# PCB_Master_Traffic_Light.net
KiCad netlist of a schematic drawn in Altium Designer
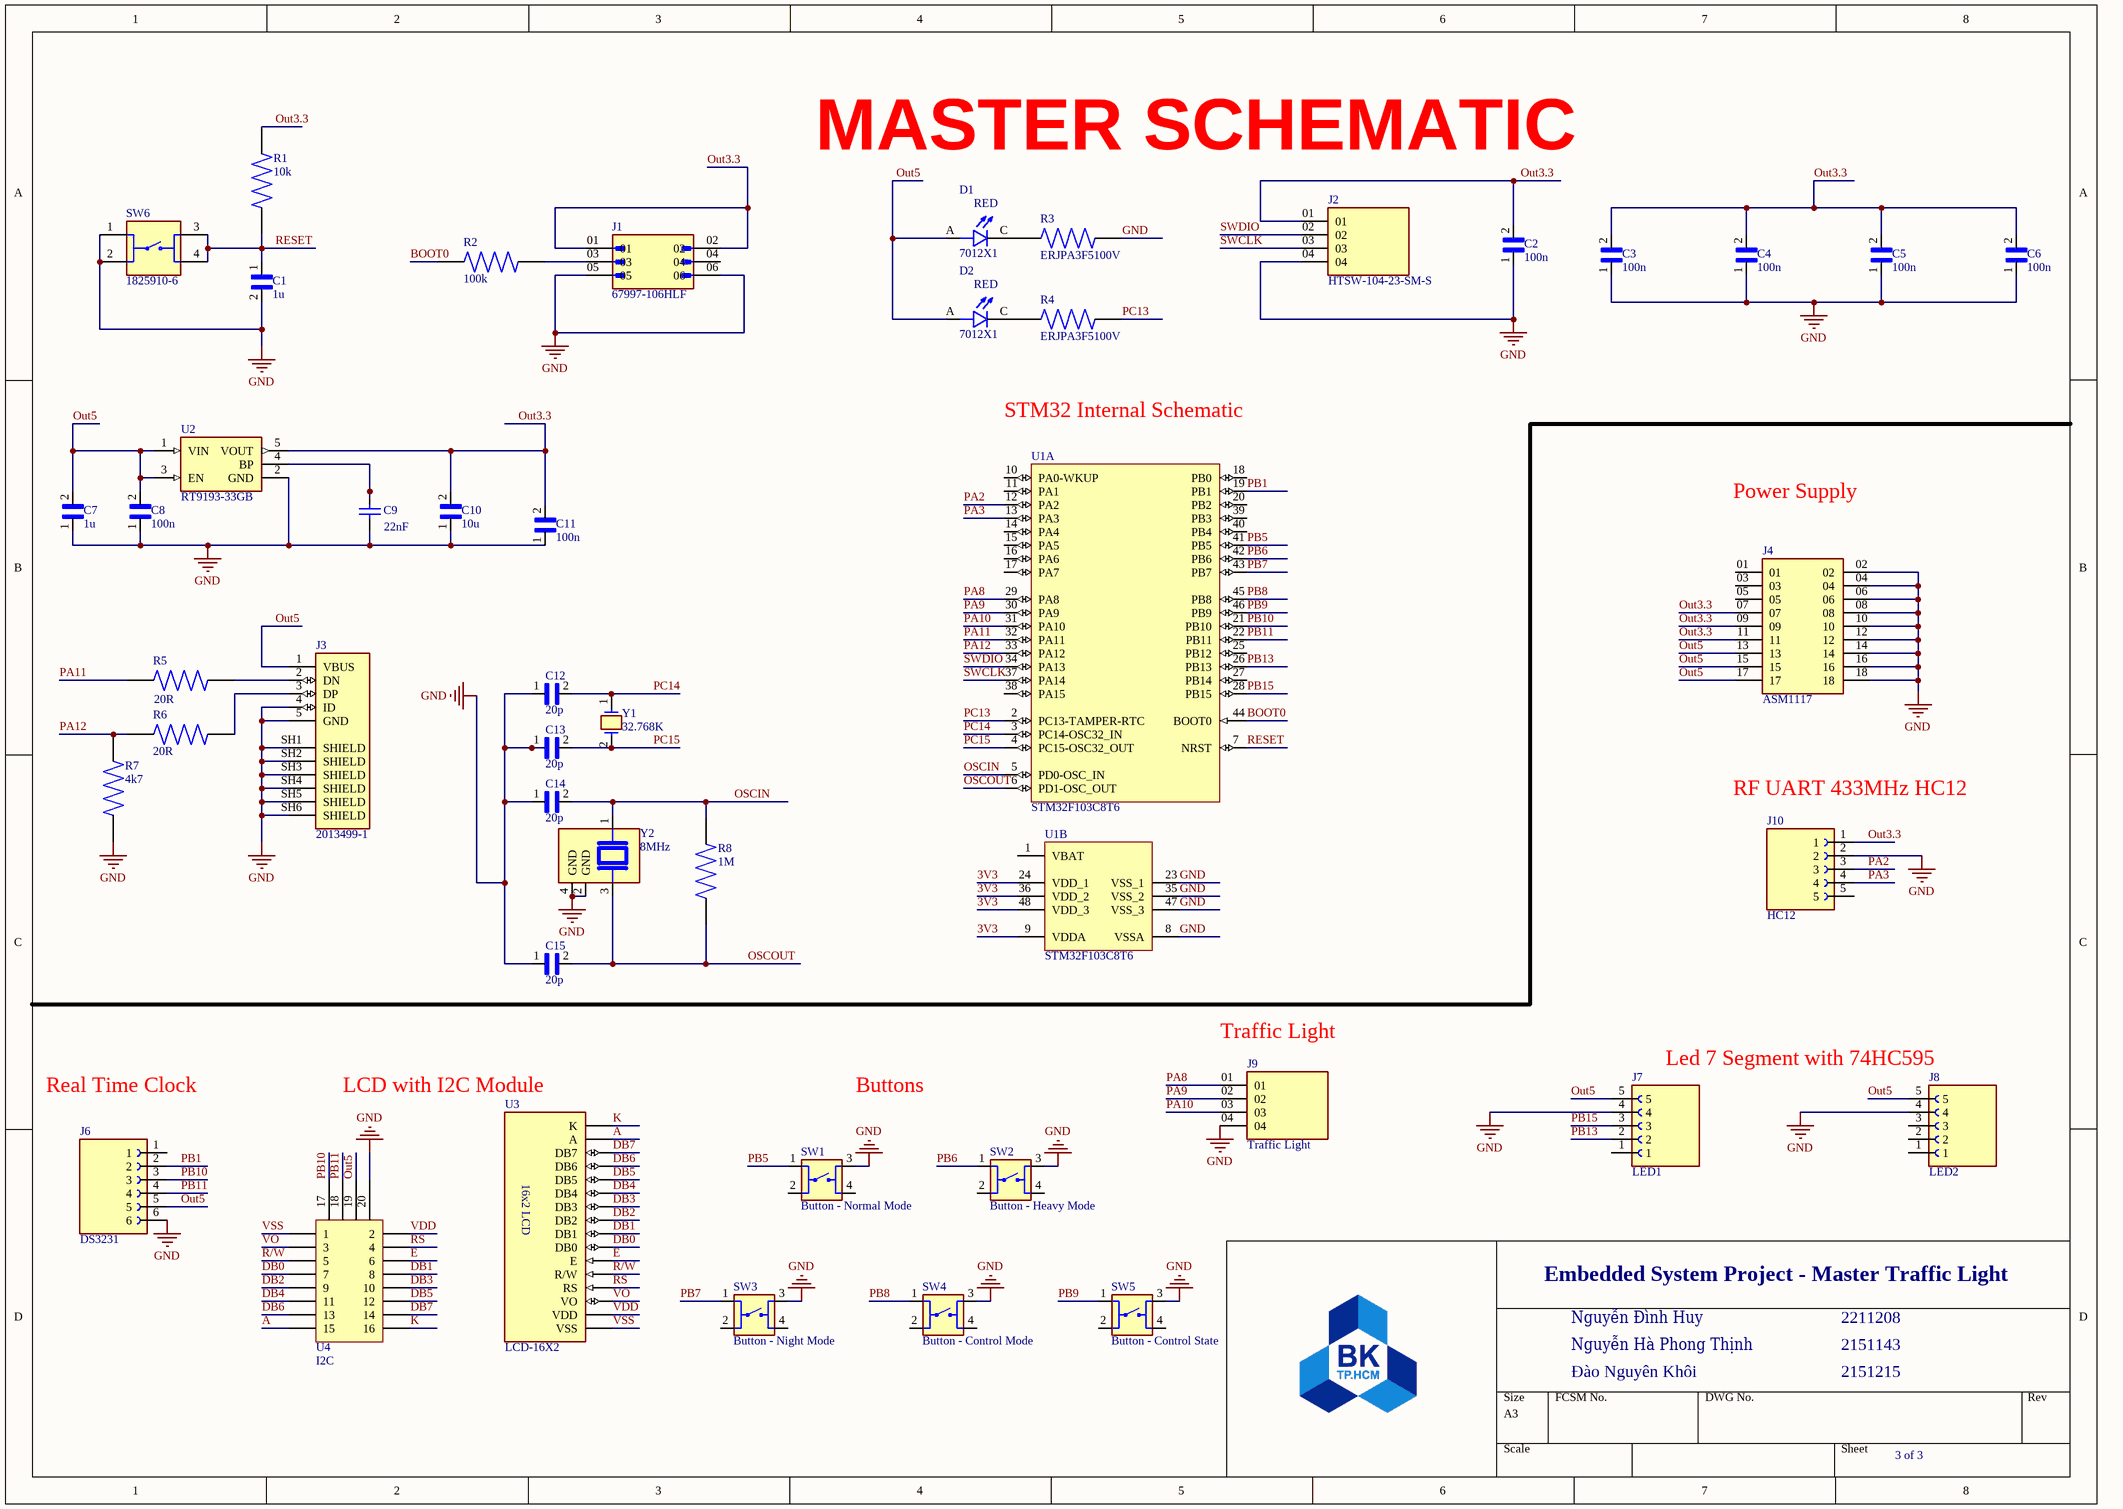
[diagram p0: PCB_Master_Traffic_Light.SchDoc]

(export (version "E")
  (design (tool "Eeschema 10.0.6"))
  (components
    (comp (ref "C1")
      (value "1u")
      (footprint "CAPC2012X145N")
      (description "1 ÂµF Â±10% 25V Ceramic Capacitor X5R 0805 (2012 Metric)")
      (fields (field (name "MF") "TDK") (field (name "DIGI-KEY_PART_NUMBER") "445-1419-2-ND"))
      (libsource (lib "Capacitor 1u") (part "C2012X5R1E105K125AA"))
    )
    (comp (ref "C2")
      (value "100n")
      (footprint "CAPC2012X100N")
      (description "0.1 ÂµF Â±10% 50V Ceramic Capacitor X7R 0805 (2012 Metric)")
      (fields (field (name "MP") "C2012X7R1H104K085AA") (field (name "MF") "TDK"))
      (libsource (lib "Capacitor 100n") (part "C2012X7R1H104K085AA"))
    )
    (comp (ref "C3")
      (value "100n")
      (footprint "CAPC2012X100N")
      (description "0.1 ÂµF Â±10% 50V Ceramic Capacitor X7R 0805 (2012 Metric)")
      (fields (field (name "MP") "C2012X7R1H104K085AA") (field (name "MF") "TDK"))
      (libsource (lib "Capacitor 100n") (part "C2012X7R1H104K085AA"))
    )
    (comp (ref "C4")
      (value "100n")
      (footprint "CAPC2012X100N")
      (description "0.1 ÂµF Â±10% 50V Ceramic Capacitor X7R 0805 (2012 Metric)")
      (fields (field (name "MP") "C2012X7R1H104K085AA") (field (name "MF") "TDK"))
      (libsource (lib "Capacitor 100n") (part "C2012X7R1H104K085AA"))
    )
    (comp (ref "C5")
      (value "100n")
      (footprint "CAPC2012X100N")
      (description "0.1 ÂµF Â±10% 50V Ceramic Capacitor X7R 0805 (2012 Metric)")
      (fields (field (name "MP") "C2012X7R1H104K085AA") (field (name "MF") "TDK"))
      (libsource (lib "Capacitor 100n") (part "C2012X7R1H104K085AA"))
    )
    (comp (ref "C6")
      (value "100n")
      (footprint "CAPC2012X100N")
      (description "0.1 ÂµF Â±10% 50V Ceramic Capacitor X7R 0805 (2012 Metric)")
      (fields (field (name "MP") "C2012X7R1H104K085AA") (field (name "MF") "TDK"))
      (libsource (lib "Capacitor 100n") (part "C2012X7R1H104K085AA"))
    )
    (comp (ref "C7")
      (value "1u")
      (footprint "CAPC2012X145N")
      (description "1 ÂµF Â±10% 25V Ceramic Capacitor X5R 0805 (2012 Metric)")
      (fields (field (name "MF") "TDK") (field (name "DIGI-KEY_PART_NUMBER") "445-1419-2-ND"))
      (libsource (lib "") (part "C2012X5R1E105K125AA_1"))
    )
    (comp (ref "C8")
      (value "100n")
      (footprint "CAPC2012X100N")
      (description "0.1 ÂµF Â±10% 50V Ceramic Capacitor X7R 0805 (2012 Metric)")
      (fields (field (name "MP") "C2012X7R1H104K085AA") (field (name "MF") "TDK"))
      (libsource (lib "Capacitor 100n") (part "C2012X7R1H104K085AA"))
    )
    (comp (ref "C9")
      (value "22nF")
      (footprint "WCAP-CSGP_1812_L4.5W3.2H1.25")
      (description "WCAP-CSGP Multilayer Ceramic Chip Capacitor, General Purpose, size 1812, NP0, 22nF, 50V")
      (fields
        (field (name "MANUFACTURER PART NUMBER") "885012010015")
        (field (name "MANUFACTURER") "Wurth Elektronik")
      )
      (libsource (lib "Capacitor 22n") (part "885012010015"))
    )
    (comp (ref "C10")
      (value "10u")
      (footprint "CAPC2012X100N")
      (description "10ÂµF Â±20% 16V Ceramic Capacitor X5R 0805 (2012 Metric)")
      (fields (field (name "MF") "TDK") (field (name "MP") "C2012X5R1C106M085AC"))
      (libsource (lib "Capacitor 10u") (part "C2012X5R1C106M085AC"))
    )
    (comp (ref "C11")
      (value "100n")
      (footprint "CAPC2012X100N")
      (description "0.1 ÂµF Â±10% 50V Ceramic Capacitor X7R 0805 (2012 Metric)")
      (fields (field (name "MP") "C2012X7R1H104K085AA") (field (name "MF") "TDK"))
      (libsource (lib "Capacitor 100n") (part "C2012X7R1H104K085AA"))
    )
    (comp (ref "C12")
      (value "20p")
      (footprint "CAPC2012X100N")
      (description "SMD Capacitor C0G(EIA) with Capacitance: 20pF Tol. 5%. Rated Voltage: 250Vdc")
      (fields (field (name "MF") "Murata") (field (name "MP") "GQM2195C2E200JB12D"))
      (libsource (lib "Capacitor 20pF") (part "GQM2195C2E200JB12D"))
    )
    (comp (ref "C13")
      (value "20p")
      (footprint "CAPC2012X100N")
      (description "SMD Capacitor C0G(EIA) with Capacitance: 20pF Tol. 5%. Rated Voltage: 250Vdc")
      (fields (field (name "MF") "Murata") (field (name "MP") "GQM2195C2E200JB12D"))
      (libsource (lib "Capacitor 20pF") (part "GQM2195C2E200JB12D"))
    )
    (comp (ref "C14")
      (value "20p")
      (footprint "CAPC2012X100N")
      (description "SMD Capacitor C0G(EIA) with Capacitance: 20pF Tol. 5%. Rated Voltage: 250Vdc")
      (fields (field (name "MF") "Murata") (field (name "MP") "GQM2195C2E200JB12D"))
      (libsource (lib "Capacitor 20pF") (part "GQM2195C2E200JB12D"))
    )
    (comp (ref "C15")
      (value "20p")
      (footprint "CAPC2012X100N")
      (description "SMD Capacitor C0G(EIA) with Capacitance: 20pF Tol. 5%. Rated Voltage: 250Vdc")
      (fields (field (name "MF") "Murata") (field (name "MP") "GQM2195C2E200JB12D"))
      (libsource (lib "Capacitor 20pF") (part "GQM2195C2E200JB12D"))
    )
    (comp (ref "D1")
      (value "7012X1")
      (footprint "LED_7012X1")
      (description "Red - LED Indication - Discrete 1.7V 0805 (2012 Metric)")
      (fields (field (name "MF") "VCC"))
      (libsource (lib "RedLed") (part "7012X1"))
    )
    (comp (ref "D2")
      (value "7012X1")
      (footprint "LED_7012X1")
      (description "Red - LED Indication - Discrete 1.7V 0805 (2012 Metric)")
      (fields (field (name "MF") "VCC"))
      (libsource (lib "RedLed") (part "7012X1"))
    )
    (comp (ref "J1")
      (value "67997-106HLF")
      (footprint "AMPHENOL_67997-106HLF")
      (fields (field (name "MF") "Amphenol ICC"))
      (libsource (lib "Header3x2") (part "67997-106HLF"))
    )
    (comp (ref "J2")
      (value "HTSW-104-23-SM-S")
      (footprint "SAMTEC_HTSW-104-23-SM-S")
      (fields (field (name "MF") "Samtec") (field (name "MP") "HTSW10423SMS"))
      (libsource (lib "Header 4x1") (part "HTSW-104-23-SM-S"))
    )
    (comp (ref "J3")
      (value "2013499-1")
      (footprint "TE_2013499-1")
      (libsource (lib "micro USB") (part "2013499-1"))
    )
    (comp (ref "J4")
      (value "ASM1117")
      (footprint "SAMTEC_MTSW-109-13-G-D-905")
      (fields (field (name "MP") "MTSW-109-13-G-D-905"))
      (libsource (lib "Header 9x2") (part "MTSW-109-13-G-D-905"))
    )
    (comp (ref "J6")
      (value "DS3231")
      (footprint "HARWIN_M20-7820646")
      (fields (field (name "MP") "M20-7820646"))
      (libsource (lib "Header 6x1") (part "M20-7820646"))
    )
    (comp (ref "J7")
      (value "LED1")
      (footprint "HARWIN_M20-7820546")
      (fields (field (name "MP") "M20-7820546"))
      (libsource (lib "") (part "M20-7820546_1"))
    )
    (comp (ref "J8")
      (value "LED2")
      (footprint "HARWIN_M20-7820546")
      (fields (field (name "MP") "M20-7820546"))
      (libsource (lib "") (part "M20-7820546_1"))
    )
    (comp (ref "J9")
      (value "Traffic Light")
      (footprint "SAMTEC_HTSW-104-23-SM-S")
      (fields (field (name "MF") "Samtec") (field (name "MP") "HTSW10423SMS"))
      (libsource (lib "Header 4x1") (part "HTSW-104-23-SM-S"))
    )
    (comp (ref "J10")
      (value "HC12")
      (footprint "HARWIN_M20-7820546")
      (fields (field (name "MP") "M20-7820546"))
      (libsource (lib "Header 5x1") (part "M20-7820546"))
    )
    (comp (ref "R1")
      (value "10k")
      (footprint "RESC2012X60N")
      (description "10 kOhms Â±1% 0.125W, 1/8W Chip Resistor 0805 (2012 Metric) Moisture Resistant Thick Film")
      (fields (field (name "MF") "Yageo") (field (name "MP") "RC0805FR-0710KL"))
      (libsource (lib "RES10k") (part "RC0805FR-0710KL"))
    )
    (comp (ref "R2")
      (value "100k")
      (footprint "RESC2012X60N")
      (description "100 kOhms Â±1% 0.125W, 1/8W Chip Resistor 0805 (2012 Metric) Moisture Resistant Thick Film")
      (fields (field (name "MF") "Yageo") (field (name "MP") "RC0805FR-07100KL"))
      (libsource (lib "RES100k") (part "RC0805FR-07100KL"))
    )
    (comp (ref "R3")
      (value "ERJPA3F5100V")
      (footprint "RES_ERJPA3F5100V")
      (description "RES, THICK FILM, 510R, 1%, 0.25W, 0603")
      (fields (field (name "MF") "Panasonic") (field (name "MP") "ERJ-PA3F5100V"))
      (libsource (lib "RES510") (part "ERJPA3F5100V"))
    )
    (comp (ref "R4")
      (value "ERJPA3F5100V")
      (footprint "RES_ERJPA3F5100V")
      (description "RES, THICK FILM, 510R, 1%, 0.25W, 0603")
      (fields (field (name "MF") "Panasonic") (field (name "MP") "ERJ-PA3F5100V"))
      (libsource (lib "RES510") (part "ERJPA3F5100V"))
    )
    (comp (ref "R5")
      (value "20R")
      (footprint "RESC5025X120N")
      (fields (field (name "MP") "3-2176397-2"))
      (libsource (lib "RES20") (part "3-2176397-2"))
    )
    (comp (ref "R6")
      (value "20R")
      (footprint "RESC5025X120N")
      (fields (field (name "MP") "3-2176397-2"))
      (libsource (lib "RES20") (part "3-2176397-2"))
    )
    (comp (ref "R7")
      (value "4k7")
      (footprint "RESC1608X55N")
      (fields
        (field (name "MF") "TE Connectivity")
        (field (name "MP") "CRG0603F4K7")
        (field (name "TOLERANCE") "1%")
      )
      (libsource (lib "RES4.7k") (part "CRG0603F4K7"))
    )
    (comp (ref "R8")
      (value "1M")
      (footprint "RESC2012X60N")
      (description "1 MOhms Â±1% 0.125W, 1/8W Chip Resistor 0805 (2012 Metric) Moisture Resistant Thick Film")
      (fields (field (name "MF") "Yageo") (field (name "MP") "RC0805FR-071ML"))
      (libsource (lib "RES1M") (part "RC0805FR-071ML"))
    )
    (comp (ref "SW1")
      (value "Button - Normal Mode")
      (footprint "SW_FSM8JH")
      (description "Tactile Switch SPST-NO Top Actuated Through Hole")
      (fields (field (name "MP") "FSM8JH") (field (name "MF") "TE Connectivity"))
      (libsource (lib "Button1") (part "FSM8JH"))
    )
    (comp (ref "SW2")
      (value "Button - Heavy Mode")
      (footprint "SW_FSM8JH")
      (description "Tactile Switch SPST-NO Top Actuated Through Hole")
      (fields (field (name "MP") "FSM8JH") (field (name "MF") "TE Connectivity"))
      (libsource (lib "Button1") (part "FSM8JH"))
    )
    (comp (ref "SW3")
      (value "Button - Night Mode")
      (footprint "SW_FSM8JH")
      (description "Tactile Switch SPST-NO Top Actuated Through Hole")
      (fields (field (name "MP") "FSM8JH") (field (name "MF") "TE Connectivity"))
      (libsource (lib "Button1") (part "FSM8JH"))
    )
    (comp (ref "SW4")
      (value "Button - Control Mode")
      (footprint "SW_FSM8JH")
      (description "Tactile Switch SPST-NO Top Actuated Through Hole")
      (fields (field (name "MP") "FSM8JH") (field (name "MF") "TE Connectivity"))
      (libsource (lib "Button1") (part "FSM8JH"))
    )
    (comp (ref "SW5")
      (value "Button - Control State")
      (footprint "SW_FSM8JH")
      (description "Tactile Switch SPST-NO Top Actuated Through Hole")
      (fields (field (name "MP") "FSM8JH") (field (name "MF") "TE Connectivity"))
      (libsource (lib "Button1") (part "FSM8JH"))
    )
    (comp (ref "SW6")
      (value "1825910-6")
      (footprint "SW_1825910-6-4")
      (description "Switch Push Button OFF (ON) SPST Round Button 0.05A 24VDC Momentary Contact PC Pins Thru-Hole")
      (fields (field (name "MF") "TE Connectivity") (field (name "DIGI-KEY_PART_NUMBER") "450-1650-ND"))
      (libsource (lib "Button") (part "1825910-6"))
    )
    (comp (ref "U1")
      (value "STM32F103C8T6")
      (footprint "STM-LQFP48_L")
      (libsource (lib "STM32F103C8T6") (part "CMP-0237-00215-3"))
    )
    (comp (ref "U2")
      (value "RT9193-33GB")
      (footprint "SOT94P279X129-5N")
      (description "Linear Voltage Regulator IC Positive Fixed 1 Output 300mA TSOT-23-5")
      (fields (field (name "MF") "Richtek USA") (field (name "DIGI-KEY_PART_NUMBER") "1028-1014-2-ND"))
      (libsource (lib "RT9193-33GB") (part "RT9193-33GB"))
    )
    (comp (ref "U3")
      (value "LCD-16X2")
      (footprint "MODULE_LCD-16X2")
      (description "Display Development Tools 16x2 Black on Green Char LCD w Backlight")
      (fields (field (name "MF") "Gravitech"))
      (libsource (lib "LCD-16X2") (part "LCD-16X2"))
    )
    (comp (ref "U4") (value "I2C") (footprint "PCF8574") (libsource (lib "PCF8574") (part "PCF8574")))
    (comp (ref "Y1")
      (value "32.768K")
      (footprint "XTAL_NX3215SA-32.768K-STD-MUA-14")
      (description "32.768kHz Â±20ppm Crystal 6pF 70 kOhms 2-SMD, No Lead  MANUFACTURER: NIHON DEMPA KOGYO")
      (fields (field (name "MP") "NX3215SA-32.768K-STD-MUA-14"))
      (libsource (lib "Crystal 32.768k") (part "NX3215SA-32.768K-STD-MUA-14"))
    )
    (comp (ref "Y2")
      (value "8MHz")
      (footprint "XTAL_ABM3B-8.000MHZ-10-1-U-T")
      (description "8 MHz Â±10ppm Crystal 10pF 200 Ohms 4-SMD, No Lead")
      (fields (field (name "MF") "Abracon") (field (name "MP") "ABM3B-8.000MHZ-10-1-U-T"))
      (libsource (lib "Crystal 8MHz") (part "ABM3B-8.000MHZ-10-1-U-T"))
    )
  )
  (nets
    (net (code "1") (name "/3V3") (class "Default")
      (node (ref "U1") (pin "24") (pinfunction "VDD_1_24") (pintype "power_in"))
      (node (ref "U1") (pin "36") (pinfunction "VDD_2_36") (pintype "power_in"))
      (node (ref "U1") (pin "48") (pinfunction "VDD_3_48") (pintype "power_in"))
      (node (ref "U1") (pin "9") (pinfunction "VDDA_9") (pintype "power_in"))
    )
    (net (code "2") (name "/A") (class "Default")
      (node (ref "U3") (pin "15") (pinfunction "A_15") (pintype "power_in"))
      (node (ref "U4") (pin "15") (pinfunction "15_15") (pintype "passive"))
    )
    (net (code "3") (name "/BOOT0") (class "Default")
      (node (ref "R2") (pin "1") (pinfunction "1_1") (pintype "passive"))
      (node (ref "U1") (pin "44") (pinfunction "BOOT0_44") (pintype "input"))
    )
    (net (code "4") (name "/DB0") (class "Default")
      (node (ref "U3") (pin "7") (pinfunction "DB0_7") (pintype "bidirectional"))
      (node (ref "U4") (pin "7") (pinfunction "7_7") (pintype "passive"))
    )
    (net (code "5") (name "/DB1") (class "Default")
      (node (ref "U3") (pin "8") (pinfunction "DB1_8") (pintype "bidirectional"))
      (node (ref "U4") (pin "8") (pinfunction "8_8") (pintype "passive"))
    )
    (net (code "6") (name "/DB2") (class "Default")
      (node (ref "U3") (pin "9") (pinfunction "DB2_9") (pintype "bidirectional"))
      (node (ref "U4") (pin "9") (pinfunction "9_9") (pintype "passive"))
    )
    (net (code "7") (name "/DB3") (class "Default")
      (node (ref "U3") (pin "10") (pinfunction "DB3_10") (pintype "bidirectional"))
      (node (ref "U4") (pin "10") (pinfunction "10_10") (pintype "passive"))
    )
    (net (code "8") (name "/DB4") (class "Default")
      (node (ref "U3") (pin "11") (pinfunction "DB4_11") (pintype "bidirectional"))
      (node (ref "U4") (pin "11") (pinfunction "11_11") (pintype "passive"))
    )
    (net (code "9") (name "/DB5") (class "Default")
      (node (ref "U3") (pin "12") (pinfunction "DB5_12") (pintype "bidirectional"))
      (node (ref "U4") (pin "12") (pinfunction "12_12") (pintype "passive"))
    )
    (net (code "10") (name "/DB6") (class "Default")
      (node (ref "U3") (pin "13") (pinfunction "DB6_13") (pintype "bidirectional"))
      (node (ref "U4") (pin "13") (pinfunction "13_13") (pintype "passive"))
    )
    (net (code "11") (name "/DB7") (class "Default")
      (node (ref "U3") (pin "14") (pinfunction "DB7_14") (pintype "bidirectional"))
      (node (ref "U4") (pin "14") (pinfunction "14_14") (pintype "passive"))
    )
    (net (code "12") (name "/E") (class "Default")
      (node (ref "U3") (pin "6") (pinfunction "E_6") (pintype "input"))
      (node (ref "U4") (pin "6") (pinfunction "6_6") (pintype "passive"))
    )
    (net (code "13") (name "/K") (class "Default")
      (node (ref "U3") (pin "16") (pinfunction "K_16") (pintype "power_in"))
      (node (ref "U4") (pin "16") (pinfunction "16_16") (pintype "passive"))
    )
    (net (code "14") (name "/OSCIN") (class "Default")
      (node (ref "C14") (pin "2") (pinfunction "2_2") (pintype "passive"))
      (node (ref "R8") (pin "2") (pinfunction "2_2") (pintype "passive"))
      (node (ref "U1") (pin "5") (pinfunction "PD0-OSC_IN_5") (pintype "bidirectional"))
      (node (ref "Y2") (pin "1") (pinfunction "1_1") (pintype "passive"))
    )
    (net (code "15") (name "/OSCOUT") (class "Default")
      (node (ref "C15") (pin "2") (pinfunction "2_2") (pintype "passive"))
      (node (ref "R8") (pin "1") (pinfunction "1_1") (pintype "passive"))
      (node (ref "U1") (pin "6") (pinfunction "PD1-OSC_OUT_6") (pintype "bidirectional"))
      (node (ref "Y2") (pin "3") (pinfunction "2_3") (pintype "passive"))
    )
    (net (code "16") (name "/Out3.3") (class "Default")
      (node (ref "C10") (pin "2") (pinfunction "2_2") (pintype "passive"))
      (node (ref "C11") (pin "2") (pinfunction "2_2") (pintype "passive"))
      (node (ref "C2") (pin "2") (pinfunction "2_2") (pintype "passive"))
      (node (ref "C3") (pin "2") (pinfunction "2_2") (pintype "passive"))
      (node (ref "C4") (pin "2") (pinfunction "2_2") (pintype "passive"))
      (node (ref "C5") (pin "2") (pinfunction "2_2") (pintype "passive"))
      (node (ref "C6") (pin "2") (pinfunction "2_2") (pintype "passive"))
      (node (ref "J1") (pin "01") (pinfunction "01_01") (pintype "passive"))
      (node (ref "J1") (pin "02") (pinfunction "02_02") (pintype "passive"))
      (node (ref "J10") (pin "1") (pinfunction "1_1") (pintype "passive"))
      (node (ref "J2") (pin "01") (pinfunction "01_01") (pintype "passive"))
      (node (ref "J4") (pin "07") (pinfunction "07_07") (pintype "passive"))
      (node (ref "J4") (pin "09") (pinfunction "09_09") (pintype "passive"))
      (node (ref "J4") (pin "11") (pinfunction "11_11") (pintype "passive"))
      (node (ref "R1") (pin "1") (pinfunction "1_1") (pintype "passive"))
      (node (ref "U2") (pin "5") (pinfunction "VOUT_5") (pintype "output"))
    )
    (net (code "17") (name "/Out5") (class "Default")
      (node (ref "C7") (pin "2") (pinfunction "2_2") (pintype "passive"))
      (node (ref "C8") (pin "2") (pinfunction "2_2") (pintype "passive"))
      (node (ref "D1") (pin "A") (pinfunction "A_A") (pintype "passive"))
      (node (ref "D2") (pin "A") (pinfunction "A_A") (pintype "passive"))
      (node (ref "J3") (pin "1") (pinfunction "VBUS_1") (pintype "power_in"))
      (node (ref "J4") (pin "13") (pinfunction "13_13") (pintype "passive"))
      (node (ref "J4") (pin "15") (pinfunction "15_15") (pintype "passive"))
      (node (ref "J4") (pin "17") (pinfunction "17_17") (pintype "passive"))
      (node (ref "J6") (pin "5") (pinfunction "5_5") (pintype "passive"))
      (node (ref "J7") (pin "5") (pinfunction "5_5") (pintype "passive"))
      (node (ref "J8") (pin "5") (pinfunction "5_5") (pintype "passive"))
      (node (ref "U2") (pin "1") (pinfunction "VIN_1") (pintype "input"))
      (node (ref "U2") (pin "3") (pinfunction "EN_3") (pintype "input"))
      (node (ref "U4") (pin "19") (pinfunction "19_19") (pintype "passive"))
    )
    (net (code "18") (name "/PA2") (class "Default")
      (node (ref "J10") (pin "3") (pinfunction "3_3") (pintype "passive"))
      (node (ref "U1") (pin "12") (pinfunction "PA2_12") (pintype "bidirectional"))
    )
    (net (code "19") (name "/PA3") (class "Default")
      (node (ref "J10") (pin "4") (pinfunction "4_4") (pintype "passive"))
      (node (ref "U1") (pin "13") (pinfunction "PA3_13") (pintype "bidirectional"))
    )
    (net (code "20") (name "/PA8") (class "Default")
      (node (ref "J9") (pin "01") (pinfunction "01_01") (pintype "passive"))
      (node (ref "U1") (pin "29") (pinfunction "PA8_29") (pintype "bidirectional"))
    )
    (net (code "21") (name "/PA9") (class "Default")
      (node (ref "J9") (pin "02") (pinfunction "02_02") (pintype "passive"))
      (node (ref "U1") (pin "30") (pinfunction "PA9_30") (pintype "bidirectional"))
    )
    (net (code "22") (name "/PA10") (class "Default")
      (node (ref "J9") (pin "03") (pinfunction "03_03") (pintype "passive"))
      (node (ref "U1") (pin "31") (pinfunction "PA10_31") (pintype "bidirectional"))
    )
    (net (code "23") (name "/PA11") (class "Default")
      (node (ref "R5") (pin "1") (pinfunction "1_1") (pintype "passive"))
      (node (ref "U1") (pin "32") (pinfunction "PA11_32") (pintype "bidirectional"))
    )
    (net (code "24") (name "/PA12") (class "Default")
      (node (ref "R6") (pin "1") (pinfunction "1_1") (pintype "passive"))
      (node (ref "R7") (pin "2") (pinfunction "2_2") (pintype "passive"))
      (node (ref "U1") (pin "33") (pinfunction "PA12_33") (pintype "bidirectional"))
    )
    (net (code "25") (name "/PB1") (class "Default")
      (node (ref "J6") (pin "2") (pinfunction "2_2") (pintype "passive"))
      (node (ref "U1") (pin "19") (pinfunction "PB1_19") (pintype "bidirectional"))
    )
    (net (code "26") (name "/PB5") (class "Default")
      (node (ref "SW1") (pin "1") (pinfunction "1_1") (pintype "passive"))
      (node (ref "U1") (pin "41") (pinfunction "PB5_41") (pintype "bidirectional"))
    )
    (net (code "27") (name "/PB6") (class "Default")
      (node (ref "SW2") (pin "1") (pinfunction "1_1") (pintype "passive"))
      (node (ref "U1") (pin "42") (pinfunction "PB6_42") (pintype "bidirectional"))
    )
    (net (code "28") (name "/PB7") (class "Default")
      (node (ref "SW3") (pin "1") (pinfunction "1_1") (pintype "passive"))
      (node (ref "U1") (pin "43") (pinfunction "PB7_43") (pintype "bidirectional"))
    )
    (net (code "29") (name "/PB8") (class "Default")
      (node (ref "SW4") (pin "1") (pinfunction "1_1") (pintype "passive"))
      (node (ref "U1") (pin "45") (pinfunction "PB8_45") (pintype "bidirectional"))
    )
    (net (code "30") (name "/PB9") (class "Default")
      (node (ref "SW5") (pin "1") (pinfunction "1_1") (pintype "passive"))
      (node (ref "U1") (pin "46") (pinfunction "PB9_46") (pintype "bidirectional"))
    )
    (net (code "31") (name "/PB10") (class "Default")
      (node (ref "J6") (pin "3") (pinfunction "3_3") (pintype "passive"))
      (node (ref "U1") (pin "21") (pinfunction "PB10_21") (pintype "bidirectional"))
      (node (ref "U4") (pin "17") (pinfunction "17_17") (pintype "passive"))
    )
    (net (code "32") (name "/PB11") (class "Default")
      (node (ref "J6") (pin "4") (pinfunction "4_4") (pintype "passive"))
      (node (ref "U1") (pin "22") (pinfunction "PB11_22") (pintype "bidirectional"))
      (node (ref "U4") (pin "18") (pinfunction "18_18") (pintype "passive"))
    )
    (net (code "33") (name "/PB13") (class "Default")
      (node (ref "J7") (pin "2") (pinfunction "2_2") (pintype "passive"))
      (node (ref "U1") (pin "26") (pinfunction "PB13_26") (pintype "bidirectional"))
    )
    (net (code "34") (name "/PB15") (class "Default")
      (node (ref "J7") (pin "3") (pinfunction "3_3") (pintype "passive"))
      (node (ref "U1") (pin "28") (pinfunction "PB15_28") (pintype "bidirectional"))
    )
    (net (code "35") (name "/PC13") (class "Default")
      (node (ref "R4") (pin "2") (pinfunction "2_2") (pintype "passive"))
      (node (ref "U1") (pin "2") (pinfunction "PC13-TAMPER-RTC_2") (pintype "bidirectional"))
    )
    (net (code "36") (name "/PC14") (class "Default")
      (node (ref "C12") (pin "2") (pinfunction "2_2") (pintype "passive"))
      (node (ref "U1") (pin "3") (pinfunction "PC14-OSC32_IN_3") (pintype "bidirectional"))
      (node (ref "Y1") (pin "1") (pinfunction "1_1") (pintype "passive"))
    )
    (net (code "37") (name "/PC15") (class "Default")
      (node (ref "C13") (pin "2") (pinfunction "2_2") (pintype "passive"))
      (node (ref "U1") (pin "4") (pinfunction "PC15-OSC32_OUT_4") (pintype "bidirectional"))
      (node (ref "Y1") (pin "2") (pinfunction "2_2") (pintype "passive"))
    )
    (net (code "38") (name "/RESET") (class "Default")
      (node (ref "C1") (pin "1") (pinfunction "1_1") (pintype "passive"))
      (node (ref "R1") (pin "2") (pinfunction "2_2") (pintype "passive"))
      (node (ref "SW6") (pin "3") (pinfunction "3_3") (pintype "passive"))
      (node (ref "SW6") (pin "4") (pinfunction "4_4") (pintype "passive"))
      (node (ref "U1") (pin "7") (pinfunction "NRST_7") (pintype "bidirectional"))
    )
    (net (code "39") (name "/RS") (class "Default")
      (node (ref "U3") (pin "4") (pinfunction "RS_4") (pintype "input"))
      (node (ref "U4") (pin "4") (pinfunction "4_4") (pintype "passive"))
    )
    (net (code "40") (name "/R{slash}W") (class "Default")
      (node (ref "U3") (pin "5") (pinfunction "R/W_5") (pintype "input"))
      (node (ref "U4") (pin "5") (pinfunction "5_5") (pintype "passive"))
    )
    (net (code "41") (name "/SWCLK") (class "Default")
      (node (ref "J2") (pin "03") (pinfunction "03_03") (pintype "passive"))
      (node (ref "U1") (pin "37") (pinfunction "PA14_37") (pintype "bidirectional"))
    )
    (net (code "42") (name "/SWDIO") (class "Default")
      (node (ref "J2") (pin "02") (pinfunction "02_02") (pintype "passive"))
      (node (ref "U1") (pin "34") (pinfunction "PA13_34") (pintype "bidirectional"))
    )
    (net (code "43") (name "/VDD") (class "Default")
      (node (ref "U3") (pin "2") (pinfunction "VDD_2") (pintype "power_in"))
      (node (ref "U4") (pin "2") (pinfunction "2_2") (pintype "passive"))
    )
    (net (code "44") (name "/VO") (class "Default")
      (node (ref "U3") (pin "3") (pinfunction "VO_3") (pintype "bidirectional"))
      (node (ref "U4") (pin "3") (pinfunction "3_3") (pintype "passive"))
    )
    (net (code "45") (name "/VSS") (class "Default")
      (node (ref "U3") (pin "1") (pinfunction "VSS_1") (pintype "power_in"))
      (node (ref "U4") (pin "1") (pinfunction "1_1") (pintype "passive"))
    )
    (net (code "46") (name "GND") (class "Default")
      (node (ref "C1") (pin "2") (pinfunction "2_2") (pintype "passive"))
      (node (ref "C10") (pin "1") (pinfunction "1_1") (pintype "passive"))
      (node (ref "C11") (pin "1") (pinfunction "1_1") (pintype "passive"))
      (node (ref "C12") (pin "1") (pinfunction "1_1") (pintype "passive"))
      (node (ref "C13") (pin "1") (pinfunction "1_1") (pintype "passive"))
      (node (ref "C14") (pin "1") (pinfunction "1_1") (pintype "passive"))
      (node (ref "C15") (pin "1") (pinfunction "1_1") (pintype "passive"))
      (node (ref "C2") (pin "1") (pinfunction "1_1") (pintype "passive"))
      (node (ref "C3") (pin "1") (pinfunction "1_1") (pintype "passive"))
      (node (ref "C4") (pin "1") (pinfunction "1_1") (pintype "passive"))
      (node (ref "C5") (pin "1") (pinfunction "1_1") (pintype "passive"))
      (node (ref "C6") (pin "1") (pinfunction "1_1") (pintype "passive"))
      (node (ref "C7") (pin "1") (pinfunction "1_1") (pintype "passive"))
      (node (ref "C8") (pin "1") (pinfunction "1_1") (pintype "passive"))
      (node (ref "C9") (pin "1") (pinfunction "1_1") (pintype "passive"))
      (node (ref "J1") (pin "05") (pinfunction "05_05") (pintype "passive"))
      (node (ref "J1") (pin "06") (pinfunction "06_06") (pintype "passive"))
      (node (ref "J10") (pin "2") (pinfunction "2_2") (pintype "passive"))
      (node (ref "J2") (pin "04") (pinfunction "04_04") (pintype "passive"))
      (node (ref "J3") (pin "4") (pinfunction "ID_4") (pintype "bidirectional"))
      (node (ref "J3") (pin "5") (pinfunction "GND_5") (pintype "power_in"))
      (node (ref "J3") (pin "SH1") (pinfunction "SHIELD_SH1") (pintype "passive"))
      (node (ref "J3") (pin "SH2") (pinfunction "SHIELD_SH2") (pintype "passive"))
      (node (ref "J3") (pin "SH3") (pinfunction "SHIELD_SH3") (pintype "passive"))
      (node (ref "J3") (pin "SH4") (pinfunction "SHIELD_SH4") (pintype "passive"))
      (node (ref "J3") (pin "SH5") (pinfunction "SHIELD_SH5") (pintype "passive"))
      (node (ref "J3") (pin "SH6") (pinfunction "SHIELD_SH6") (pintype "passive"))
      (node (ref "J4") (pin "02") (pinfunction "02_02") (pintype "passive"))
      (node (ref "J4") (pin "04") (pinfunction "04_04") (pintype "passive"))
      (node (ref "J4") (pin "06") (pinfunction "06_06") (pintype "passive"))
      (node (ref "J4") (pin "08") (pinfunction "08_08") (pintype "passive"))
      (node (ref "J4") (pin "10") (pinfunction "10_10") (pintype "passive"))
      (node (ref "J4") (pin "12") (pinfunction "12_12") (pintype "passive"))
      (node (ref "J4") (pin "14") (pinfunction "14_14") (pintype "passive"))
      (node (ref "J4") (pin "16") (pinfunction "16_16") (pintype "passive"))
      (node (ref "J4") (pin "18") (pinfunction "18_18") (pintype "passive"))
      (node (ref "J6") (pin "6") (pinfunction "6_6") (pintype "passive"))
      (node (ref "J7") (pin "4") (pinfunction "4_4") (pintype "passive"))
      (node (ref "J8") (pin "4") (pinfunction "4_4") (pintype "passive"))
      (node (ref "J9") (pin "04") (pinfunction "04_04") (pintype "passive"))
      (node (ref "R3") (pin "2") (pinfunction "2_2") (pintype "passive"))
      (node (ref "R7") (pin "1") (pinfunction "1_1") (pintype "passive"))
      (node (ref "SW1") (pin "3") (pinfunction "3_3") (pintype "passive"))
      (node (ref "SW2") (pin "3") (pinfunction "3_3") (pintype "passive"))
      (node (ref "SW3") (pin "3") (pinfunction "3_3") (pintype "passive"))
      (node (ref "SW4") (pin "3") (pinfunction "3_3") (pintype "passive"))
      (node (ref "SW5") (pin "3") (pinfunction "3_3") (pintype "passive"))
      (node (ref "SW6") (pin "1") (pinfunction "1_1") (pintype "passive"))
      (node (ref "SW6") (pin "2") (pinfunction "2_2") (pintype "passive"))
      (node (ref "U1") (pin "23") (pinfunction "VSS_1_23") (pintype "power_in"))
      (node (ref "U1") (pin "35") (pinfunction "VSS_2_35") (pintype "power_in"))
      (node (ref "U1") (pin "47") (pinfunction "VSS_3_47") (pintype "power_in"))
      (node (ref "U1") (pin "8") (pinfunction "VSSA_8") (pintype "power_in"))
      (node (ref "U2") (pin "2") (pinfunction "GND_2") (pintype "power_in"))
      (node (ref "U4") (pin "20") (pinfunction "20_20") (pintype "passive"))
      (node (ref "Y2") (pin "2") (pinfunction "GND_2") (pintype "power_in"))
      (node (ref "Y2") (pin "4") (pinfunction "GND_4") (pintype "power_in"))
    )
    (net (code "47") (name "Net-(D1-PadC)") (class "Default")
      (node (ref "D1") (pin "C") (pinfunction "C_C") (pintype "passive"))
      (node (ref "R3") (pin "1") (pinfunction "1_1") (pintype "passive"))
    )
    (net (code "48") (name "Net-(D2-PadC)") (class "Default")
      (node (ref "D2") (pin "C") (pinfunction "C_C") (pintype "passive"))
      (node (ref "R4") (pin "1") (pinfunction "1_1") (pintype "passive"))
    )
    (net (code "49") (name "Net-(J1-Pad03)") (class "Default")
      (node (ref "J1") (pin "03") (pinfunction "03_03") (pintype "passive"))
      (node (ref "R2") (pin "2") (pinfunction "2_2") (pintype "passive"))
    )
    (net (code "50") (name "Net-(J3-DN)") (class "Default")
      (node (ref "J3") (pin "2") (pinfunction "DN_2") (pintype "bidirectional"))
      (node (ref "R5") (pin "2") (pinfunction "2_2") (pintype "passive"))
    )
    (net (code "51") (name "Net-(J3-DP)") (class "Default")
      (node (ref "J3") (pin "3") (pinfunction "DP_3") (pintype "bidirectional"))
      (node (ref "R6") (pin "2") (pinfunction "2_2") (pintype "passive"))
    )
    (net (code "52") (name "Net-(U2-BP)") (class "Default")
      (node (ref "C9") (pin "2") (pinfunction "2_2") (pintype "passive"))
      (node (ref "U2") (pin "4") (pinfunction "BP_4") (pintype "passive"))
    )
    (net (code "53") (name "unconnected-(J1-Pad04)") (class "Default")
      (node (ref "J1") (pin "04") (pinfunction "04_04") (pintype "passive"))
    )
    (net (code "54") (name "unconnected-(J4-Pad01)") (class "Default")
      (node (ref "J4") (pin "01") (pinfunction "01_01") (pintype "passive"))
    )
    (net (code "55") (name "unconnected-(J4-Pad03)") (class "Default")
      (node (ref "J4") (pin "03") (pinfunction "03_03") (pintype "passive"))
    )
    (net (code "56") (name "unconnected-(J4-Pad05)") (class "Default")
      (node (ref "J4") (pin "05") (pinfunction "05_05") (pintype "passive"))
    )
    (net (code "57") (name "unconnected-(J6-Pad1)") (class "Default")
      (node (ref "J6") (pin "1") (pinfunction "1_1") (pintype "passive"))
    )
    (net (code "58") (name "unconnected-(J7-Pad1)") (class "Default")
      (node (ref "J7") (pin "1") (pinfunction "1_1") (pintype "passive"))
    )
    (net (code "59") (name "unconnected-(J8-Pad1)") (class "Default")
      (node (ref "J8") (pin "1") (pinfunction "1_1") (pintype "passive"))
    )
    (net (code "60") (name "unconnected-(J8-Pad2)") (class "Default")
      (node (ref "J8") (pin "2") (pinfunction "2_2") (pintype "passive"))
    )
    (net (code "61") (name "unconnected-(J8-Pad3)") (class "Default")
      (node (ref "J8") (pin "3") (pinfunction "3_3") (pintype "passive"))
    )
    (net (code "62") (name "unconnected-(J10-Pad5)") (class "Default")
      (node (ref "J10") (pin "5") (pinfunction "5_5") (pintype "passive"))
    )
    (net (code "63") (name "unconnected-(SW1-Pad2)") (class "Default")
      (node (ref "SW1") (pin "2") (pinfunction "2_2") (pintype "passive"))
    )
    (net (code "64") (name "unconnected-(SW1-Pad4)") (class "Default")
      (node (ref "SW1") (pin "4") (pinfunction "4_4") (pintype "passive"))
    )
    (net (code "65") (name "unconnected-(SW2-Pad2)") (class "Default")
      (node (ref "SW2") (pin "2") (pinfunction "2_2") (pintype "passive"))
    )
    (net (code "66") (name "unconnected-(SW2-Pad4)") (class "Default")
      (node (ref "SW2") (pin "4") (pinfunction "4_4") (pintype "passive"))
    )
    (net (code "67") (name "unconnected-(SW3-Pad2)") (class "Default")
      (node (ref "SW3") (pin "2") (pinfunction "2_2") (pintype "passive"))
    )
    (net (code "68") (name "unconnected-(SW3-Pad4)") (class "Default")
      (node (ref "SW3") (pin "4") (pinfunction "4_4") (pintype "passive"))
    )
    (net (code "69") (name "unconnected-(SW4-Pad2)") (class "Default")
      (node (ref "SW4") (pin "2") (pinfunction "2_2") (pintype "passive"))
    )
    (net (code "70") (name "unconnected-(SW4-Pad4)") (class "Default")
      (node (ref "SW4") (pin "4") (pinfunction "4_4") (pintype "passive"))
    )
    (net (code "71") (name "unconnected-(SW5-Pad2)") (class "Default")
      (node (ref "SW5") (pin "2") (pinfunction "2_2") (pintype "passive"))
    )
    (net (code "72") (name "unconnected-(SW5-Pad4)") (class "Default")
      (node (ref "SW5") (pin "4") (pinfunction "4_4") (pintype "passive"))
    )
    (net (code "73") (name "unconnected-(U1A-PA0-WKUP-Pad10)") (class "Default")
      (node (ref "U1") (pin "10") (pinfunction "PA0-WKUP_10") (pintype "bidirectional"))
    )
    (net (code "74") (name "unconnected-(U1A-PA1-Pad11)") (class "Default")
      (node (ref "U1") (pin "11") (pinfunction "PA1_11") (pintype "bidirectional"))
    )
    (net (code "75") (name "unconnected-(U1A-PA4-Pad14)") (class "Default")
      (node (ref "U1") (pin "14") (pinfunction "PA4_14") (pintype "bidirectional"))
    )
    (net (code "76") (name "unconnected-(U1A-PA5-Pad15)") (class "Default")
      (node (ref "U1") (pin "15") (pinfunction "PA5_15") (pintype "bidirectional"))
    )
    (net (code "77") (name "unconnected-(U1A-PA6-Pad16)") (class "Default")
      (node (ref "U1") (pin "16") (pinfunction "PA6_16") (pintype "bidirectional"))
    )
    (net (code "78") (name "unconnected-(U1A-PA7-Pad17)") (class "Default")
      (node (ref "U1") (pin "17") (pinfunction "PA7_17") (pintype "bidirectional"))
    )
    (net (code "79") (name "unconnected-(U1A-PA15-Pad38)") (class "Default")
      (node (ref "U1") (pin "38") (pinfunction "PA15_38") (pintype "bidirectional"))
    )
    (net (code "80") (name "unconnected-(U1A-PB0-Pad18)") (class "Default")
      (node (ref "U1") (pin "18") (pinfunction "PB0_18") (pintype "bidirectional"))
    )
    (net (code "81") (name "unconnected-(U1A-PB2-Pad20)") (class "Default")
      (node (ref "U1") (pin "20") (pinfunction "PB2_20") (pintype "bidirectional"))
    )
    (net (code "82") (name "unconnected-(U1A-PB3-Pad39)") (class "Default")
      (node (ref "U1") (pin "39") (pinfunction "PB3_39") (pintype "bidirectional"))
    )
    (net (code "83") (name "unconnected-(U1A-PB4-Pad40)") (class "Default")
      (node (ref "U1") (pin "40") (pinfunction "PB4_40") (pintype "bidirectional"))
    )
    (net (code "84") (name "unconnected-(U1A-PB12-Pad25)") (class "Default")
      (node (ref "U1") (pin "25") (pinfunction "PB12_25") (pintype "bidirectional"))
    )
    (net (code "85") (name "unconnected-(U1A-PB14-Pad27)") (class "Default")
      (node (ref "U1") (pin "27") (pinfunction "PB14_27") (pintype "bidirectional"))
    )
    (net (code "86") (name "unconnected-(U1B-VBAT-Pad1)") (class "Default")
      (node (ref "U1") (pin "1") (pinfunction "VBAT_1") (pintype "power_in"))
    )
  )
)
